# 4x2AND_OR_1.net
KiCad netlist of a schematic drawn in EAGLE
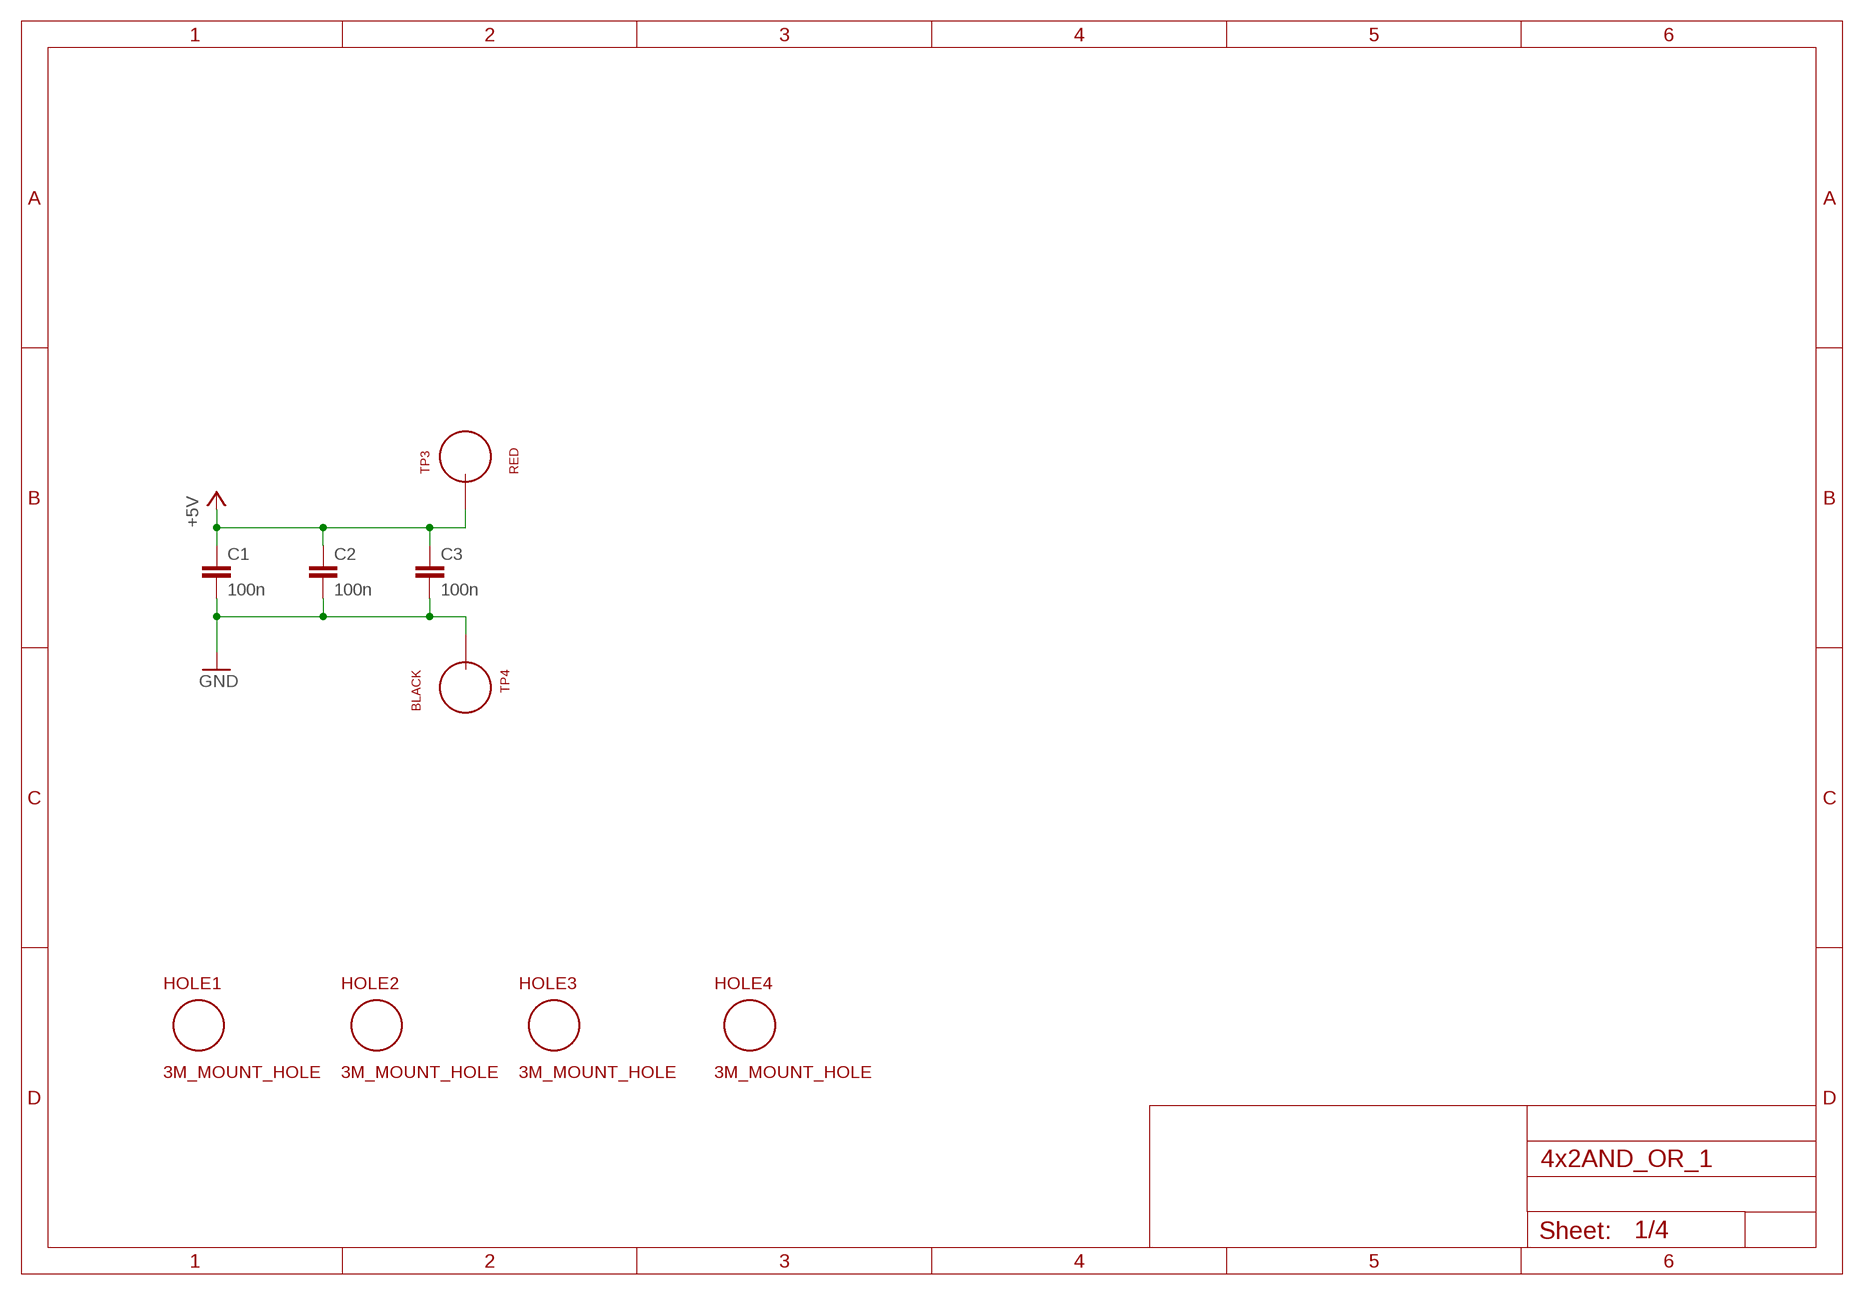
[diagram p0: schematic, sheet 1]
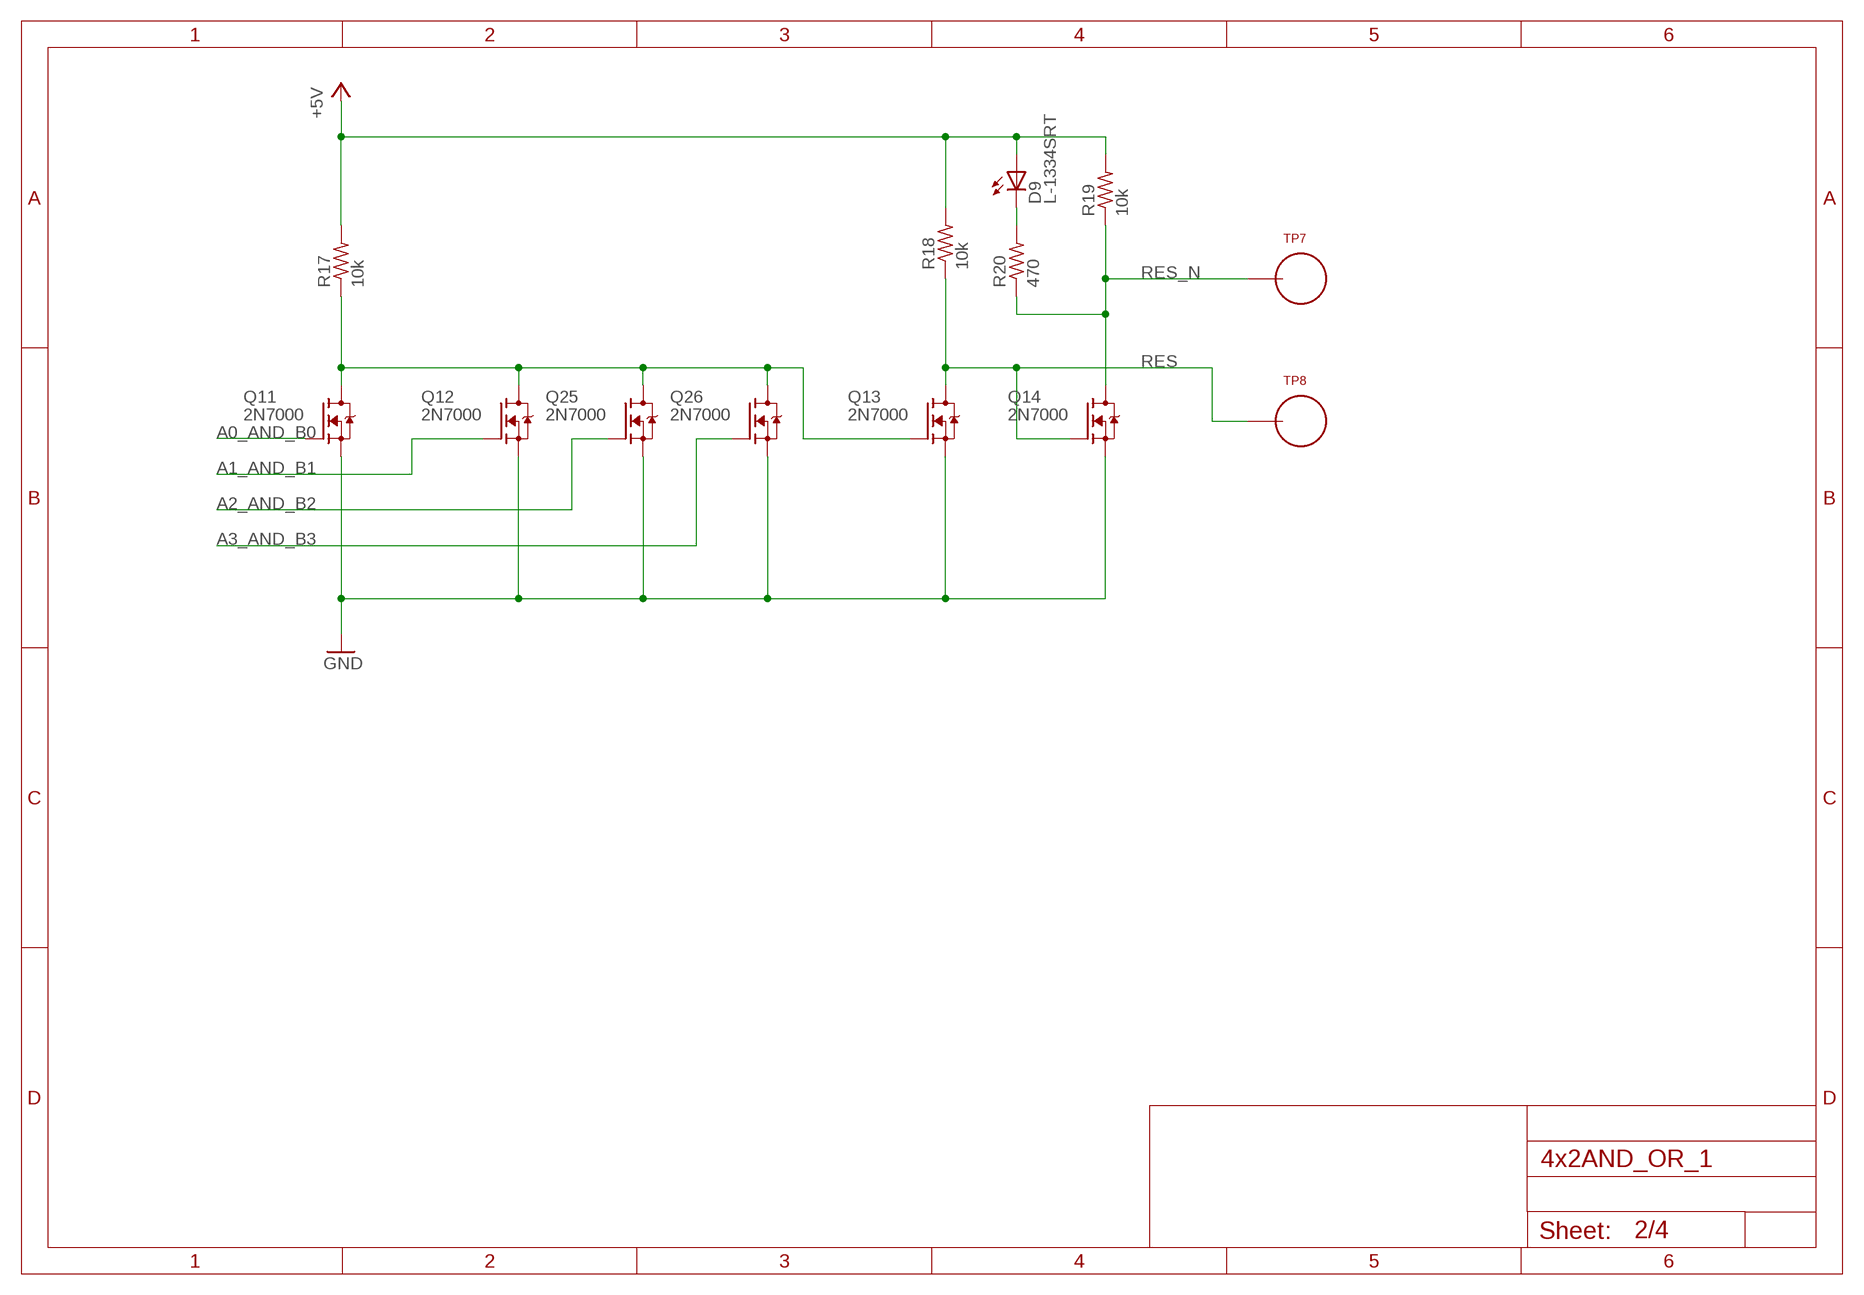
[diagram p1: schematic, sheet 2]
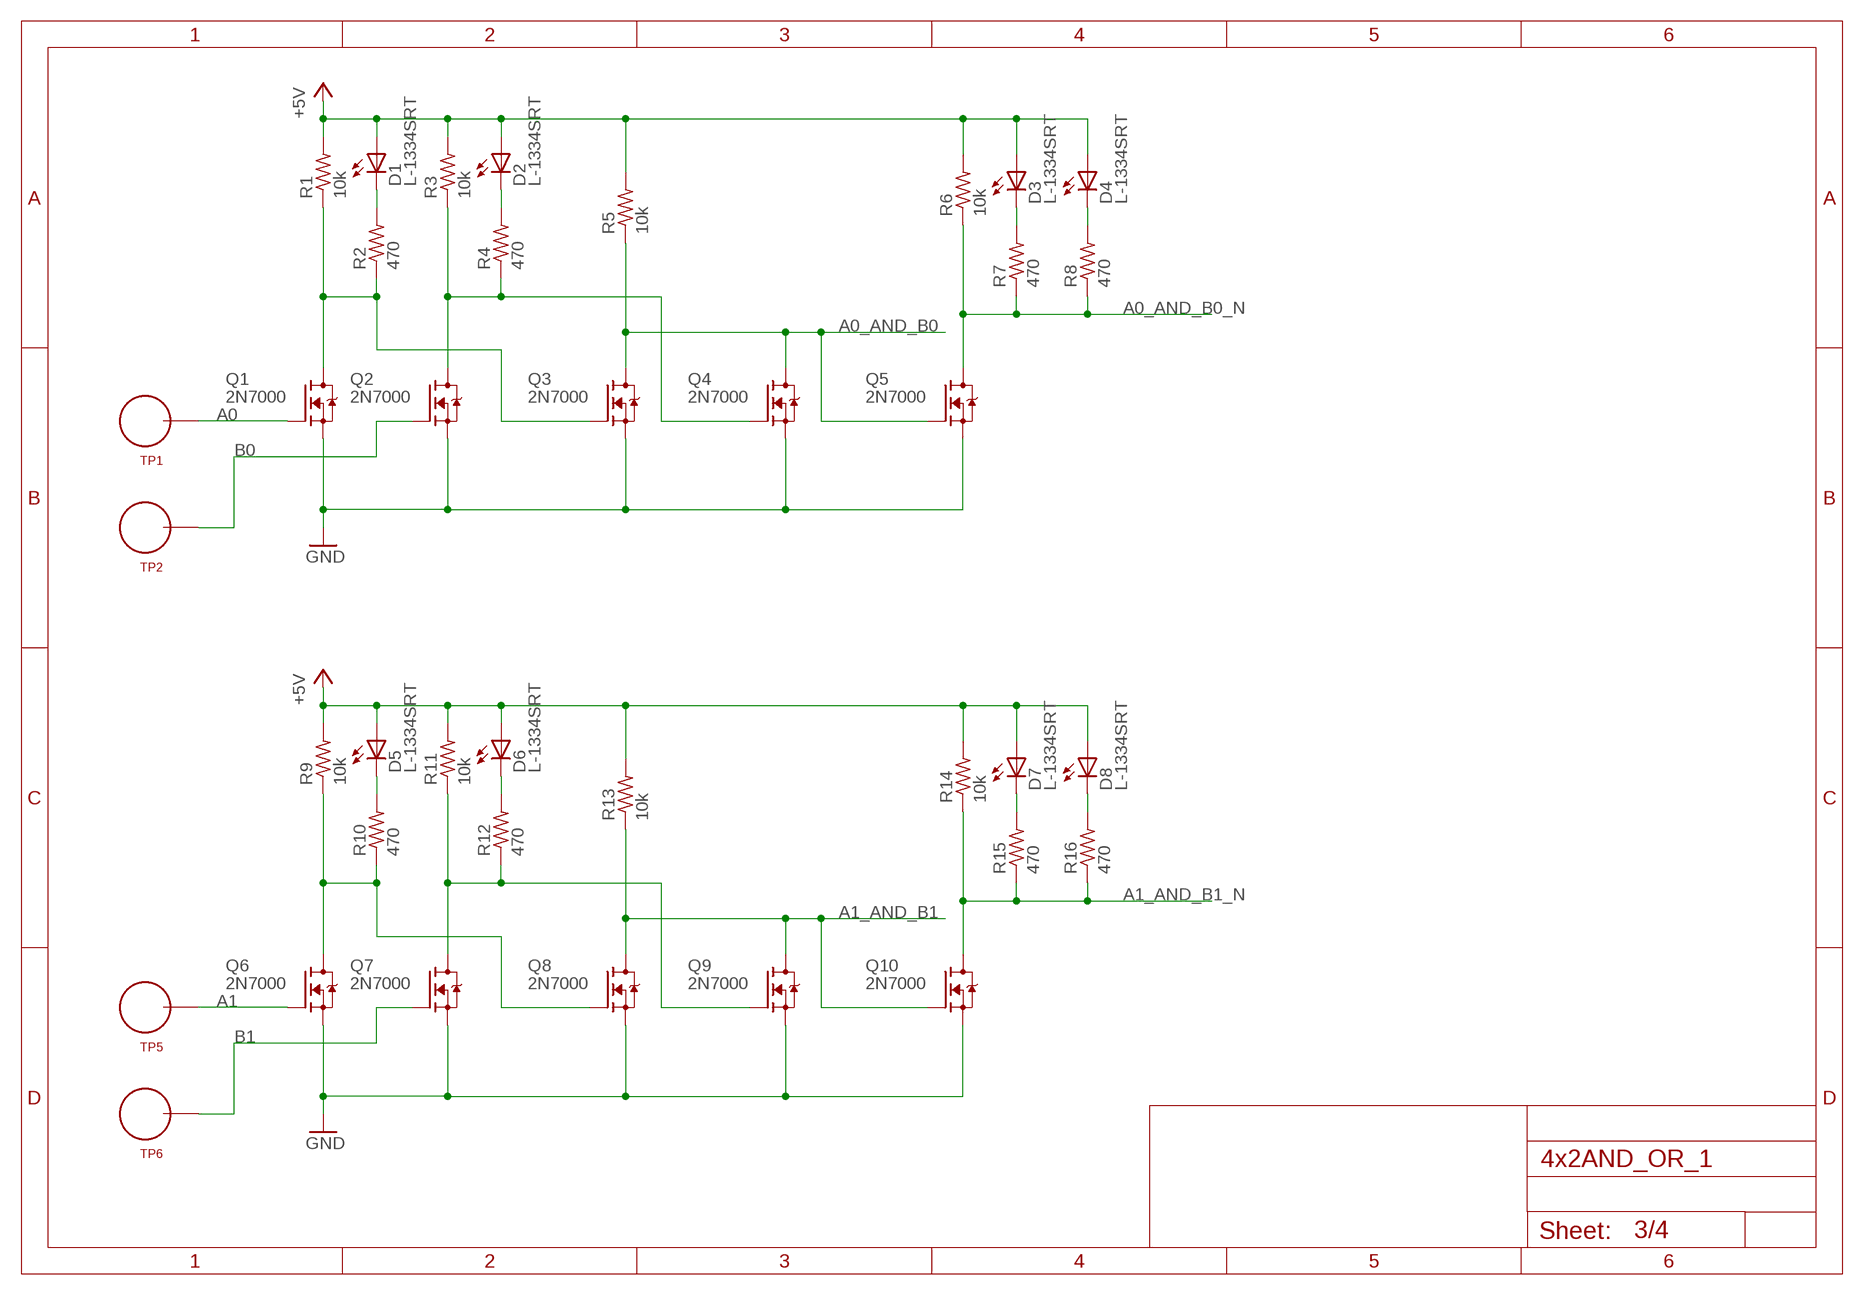
[diagram p2: schematic, sheet 3]
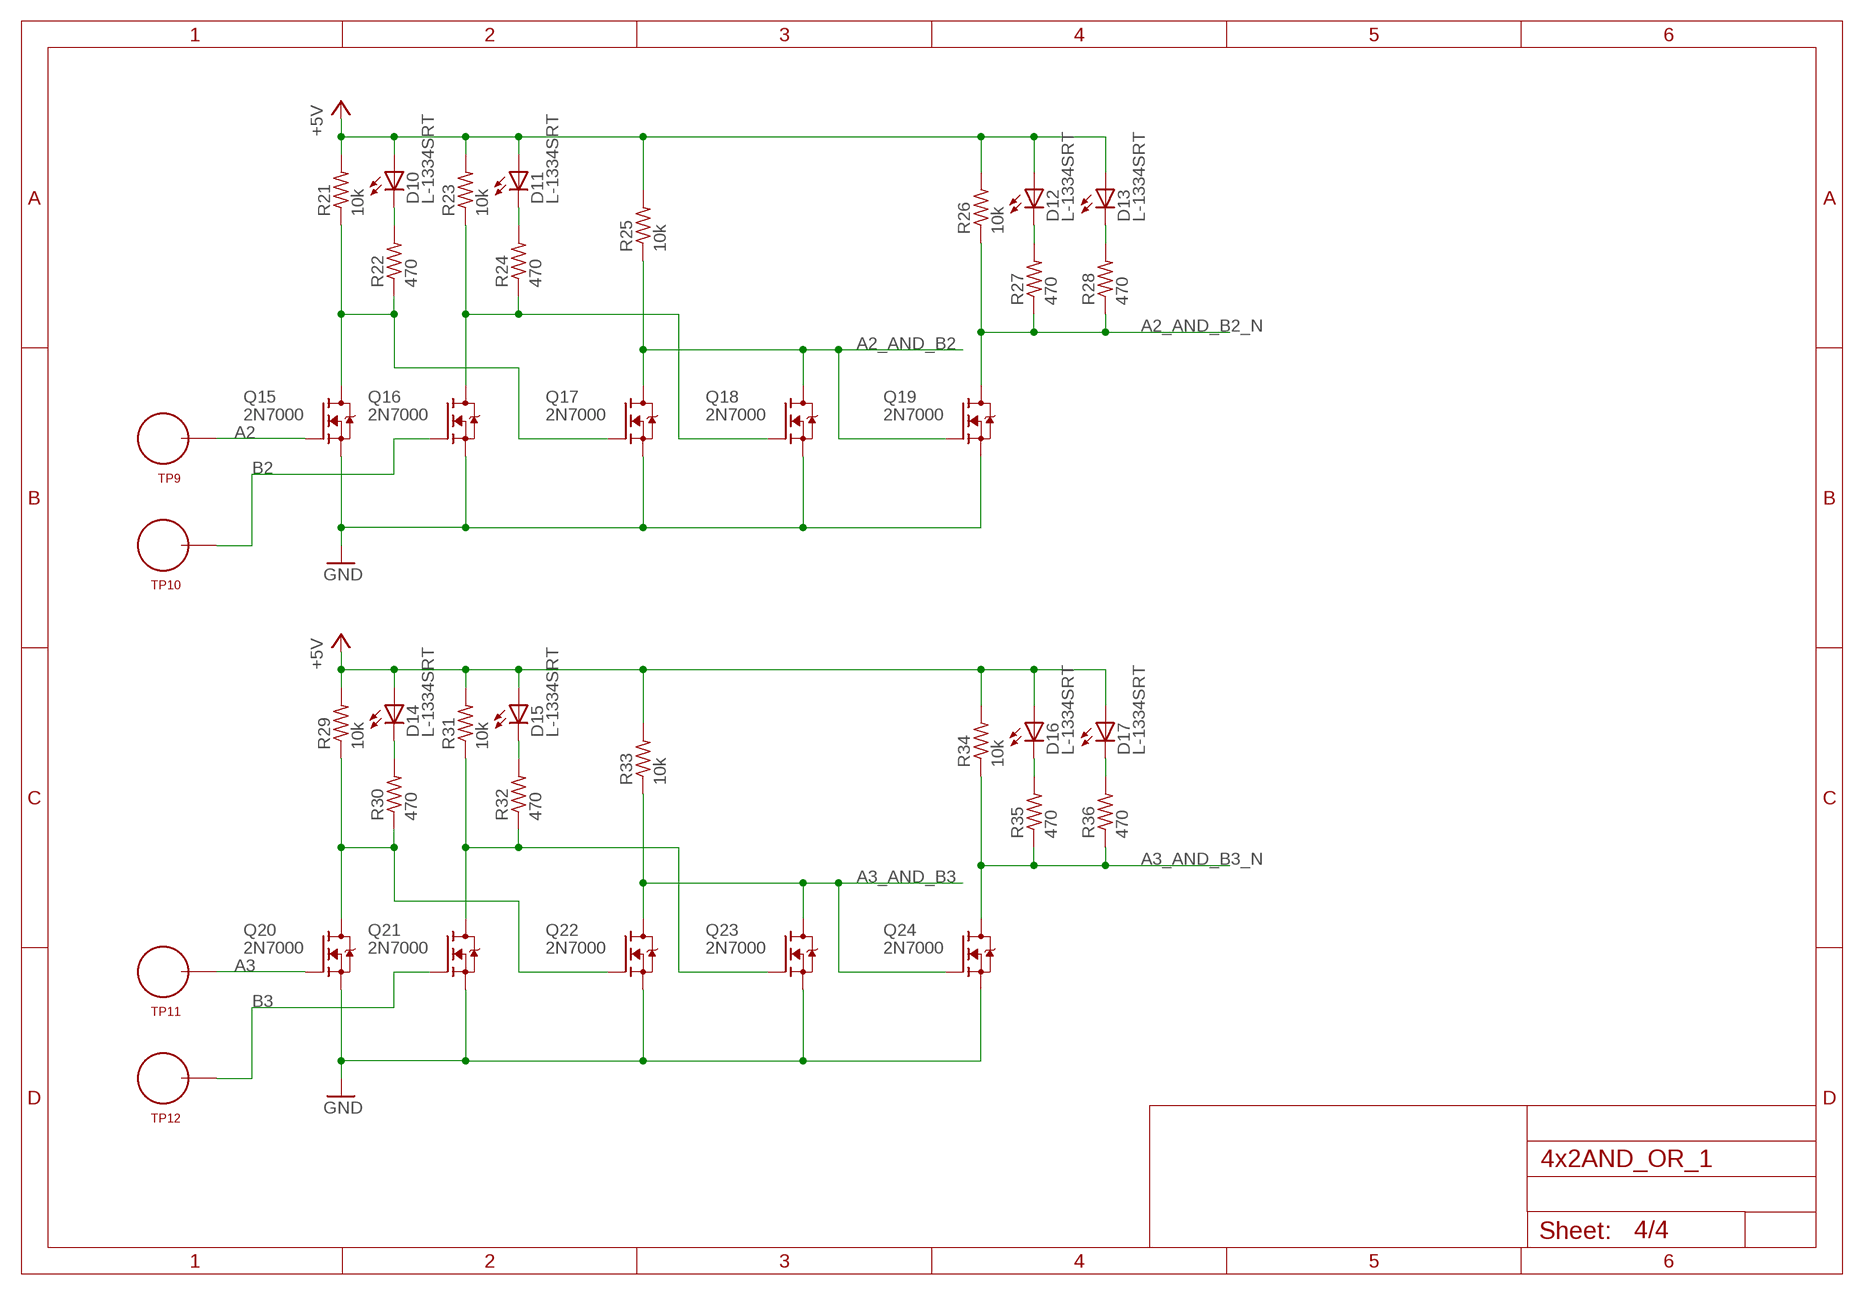
[diagram p3: schematic, sheet 4]

(export (version "E")
  (design (tool "Eeschema 10.0.6"))
  (components
    (comp (ref "D9")
      (value "L-1334SRT")
      (footprint "eagle-import:LED3MM")
      (libsource (lib "eagle-import") (part "L-1334SRT"))
    )
    (comp (ref "Q11")
      (value "2N7000")
      (footprint "eagle-import:TO92-DGS")
      (libsource (lib "eagle-import") (part "2N7000"))
    )
    (comp (ref "Q12")
      (value "2N7000")
      (footprint "eagle-import:TO92-DGS")
      (libsource (lib "eagle-import") (part "2N7000"))
    )
    (comp (ref "Q13")
      (value "2N7000")
      (footprint "eagle-import:TO92-DGS")
      (libsource (lib "eagle-import") (part "2N7000"))
    )
    (comp (ref "Q14")
      (value "2N7000")
      (footprint "eagle-import:TO92-DGS")
      (libsource (lib "eagle-import") (part "2N7000"))
    )
    (comp (ref "Q25")
      (value "2N7000")
      (footprint "eagle-import:TO92-DGS")
      (libsource (lib "eagle-import") (part "2N7000"))
    )
    (comp (ref "Q26")
      (value "2N7000")
      (footprint "eagle-import:TO92-DGS")
      (libsource (lib "eagle-import") (part "2N7000"))
    )
    (comp (ref "R17")
      (value "10k")
      (footprint "eagle-import:R_P2INCH")
      (libsource (lib "eagle-import") (part "R_P2INCH"))
    )
    (comp (ref "R18")
      (value "10k")
      (footprint "eagle-import:R_P2INCH")
      (libsource (lib "eagle-import") (part "R_P2INCH"))
    )
    (comp (ref "R19")
      (value "10k")
      (footprint "eagle-import:R_P2INCH")
      (libsource (lib "eagle-import") (part "R_P2INCH"))
    )
    (comp (ref "R20")
      (value "470")
      (footprint "eagle-import:R_P2INCH")
      (libsource (lib "eagle-import") (part "R_P2INCH"))
    )
    (comp (ref "TP7")
      (value "TEST_LOOP")
      (footprint "eagle-import:TEST_LOOP")
      (libsource (lib "eagle-import") (part "TEST_LOOP"))
    )
    (comp (ref "TP8")
      (value "TEST_LOOP")
      (footprint "eagle-import:TEST_LOOP")
      (libsource (lib "eagle-import") (part "TEST_LOOP"))
    )
    (comp (ref "C1")
      (value "100n")
      (footprint "eagle-import:CAP_P2INCH")
      (libsource (lib "eagle-import") (part "C_P2INCH"))
    )
    (comp (ref "C2")
      (value "100n")
      (footprint "eagle-import:CAP_P2INCH")
      (libsource (lib "eagle-import") (part "C_P2INCH"))
    )
    (comp (ref "C3")
      (value "100n")
      (footprint "eagle-import:CAP_P2INCH")
      (libsource (lib "eagle-import") (part "C_P2INCH"))
    )
    (comp (ref "HOLE1")
      (value "3M_MOUNT_HOLE")
      (footprint "eagle-import:3M_HOLE")
      (libsource (lib "eagle-import") (part "3M_MOUNT_HOLE"))
    )
    (comp (ref "HOLE2")
      (value "3M_MOUNT_HOLE")
      (footprint "eagle-import:3M_HOLE")
      (libsource (lib "eagle-import") (part "3M_MOUNT_HOLE"))
    )
    (comp (ref "HOLE3")
      (value "3M_MOUNT_HOLE")
      (footprint "eagle-import:3M_HOLE")
      (libsource (lib "eagle-import") (part "3M_MOUNT_HOLE"))
    )
    (comp (ref "HOLE4")
      (value "3M_MOUNT_HOLE")
      (footprint "eagle-import:3M_HOLE")
      (libsource (lib "eagle-import") (part "3M_MOUNT_HOLE"))
    )
    (comp (ref "TP3")
      (value "RED")
      (footprint "eagle-import:TEST_LOOP")
      (libsource (lib "eagle-import") (part "TEST_LOOP"))
    )
    (comp (ref "TP4")
      (value "BLACK")
      (footprint "eagle-import:TEST_LOOP")
      (libsource (lib "eagle-import") (part "TEST_LOOP"))
    )
    (comp (ref "D1")
      (value "L-1334SRT")
      (footprint "eagle-import:LED3MM")
      (libsource (lib "eagle-import") (part "L-1334SRT"))
    )
    (comp (ref "D2")
      (value "L-1334SRT")
      (footprint "eagle-import:LED3MM")
      (libsource (lib "eagle-import") (part "L-1334SRT"))
    )
    (comp (ref "D3")
      (value "L-1334SRT")
      (footprint "eagle-import:LED3MM")
      (libsource (lib "eagle-import") (part "L-1334SRT"))
    )
    (comp (ref "D4")
      (value "L-1334SRT")
      (footprint "eagle-import:LED3MM")
      (libsource (lib "eagle-import") (part "L-1334SRT"))
    )
    (comp (ref "D5")
      (value "L-1334SRT")
      (footprint "eagle-import:LED3MM")
      (libsource (lib "eagle-import") (part "L-1334SRT"))
    )
    (comp (ref "D6")
      (value "L-1334SRT")
      (footprint "eagle-import:LED3MM")
      (libsource (lib "eagle-import") (part "L-1334SRT"))
    )
    (comp (ref "D7")
      (value "L-1334SRT")
      (footprint "eagle-import:LED3MM")
      (libsource (lib "eagle-import") (part "L-1334SRT"))
    )
    (comp (ref "D8")
      (value "L-1334SRT")
      (footprint "eagle-import:LED3MM")
      (libsource (lib "eagle-import") (part "L-1334SRT"))
    )
    (comp (ref "Q1")
      (value "2N7000")
      (footprint "eagle-import:TO92-DGS")
      (libsource (lib "eagle-import") (part "2N7000"))
    )
    (comp (ref "Q2")
      (value "2N7000")
      (footprint "eagle-import:TO92-DGS")
      (libsource (lib "eagle-import") (part "2N7000"))
    )
    (comp (ref "Q3")
      (value "2N7000")
      (footprint "eagle-import:TO92-DGS")
      (libsource (lib "eagle-import") (part "2N7000"))
    )
    (comp (ref "Q4")
      (value "2N7000")
      (footprint "eagle-import:TO92-DGS")
      (libsource (lib "eagle-import") (part "2N7000"))
    )
    (comp (ref "Q5")
      (value "2N7000")
      (footprint "eagle-import:TO92-DGS")
      (libsource (lib "eagle-import") (part "2N7000"))
    )
    (comp (ref "Q6")
      (value "2N7000")
      (footprint "eagle-import:TO92-DGS")
      (libsource (lib "eagle-import") (part "2N7000"))
    )
    (comp (ref "Q7")
      (value "2N7000")
      (footprint "eagle-import:TO92-DGS")
      (libsource (lib "eagle-import") (part "2N7000"))
    )
    (comp (ref "Q8")
      (value "2N7000")
      (footprint "eagle-import:TO92-DGS")
      (libsource (lib "eagle-import") (part "2N7000"))
    )
    (comp (ref "Q9")
      (value "2N7000")
      (footprint "eagle-import:TO92-DGS")
      (libsource (lib "eagle-import") (part "2N7000"))
    )
    (comp (ref "Q10")
      (value "2N7000")
      (footprint "eagle-import:TO92-DGS")
      (libsource (lib "eagle-import") (part "2N7000"))
    )
    (comp (ref "R1")
      (value "10k")
      (footprint "eagle-import:R_P2INCH")
      (libsource (lib "eagle-import") (part "R_P2INCH"))
    )
    (comp (ref "R2")
      (value "470")
      (footprint "eagle-import:R_P2INCH")
      (libsource (lib "eagle-import") (part "R_P2INCH"))
    )
    (comp (ref "R3")
      (value "10k")
      (footprint "eagle-import:R_P2INCH")
      (libsource (lib "eagle-import") (part "R_P2INCH"))
    )
    (comp (ref "R4")
      (value "470")
      (footprint "eagle-import:R_P2INCH")
      (libsource (lib "eagle-import") (part "R_P2INCH"))
    )
    (comp (ref "R5")
      (value "10k")
      (footprint "eagle-import:R_P2INCH")
      (libsource (lib "eagle-import") (part "R_P2INCH"))
    )
    (comp (ref "R6")
      (value "10k")
      (footprint "eagle-import:R_P2INCH")
      (libsource (lib "eagle-import") (part "R_P2INCH"))
    )
    (comp (ref "R7")
      (value "470")
      (footprint "eagle-import:R_P2INCH")
      (libsource (lib "eagle-import") (part "R_P2INCH"))
    )
    (comp (ref "R8")
      (value "470")
      (footprint "eagle-import:R_P2INCH")
      (libsource (lib "eagle-import") (part "R_P2INCH"))
    )
    (comp (ref "R9")
      (value "10k")
      (footprint "eagle-import:R_P2INCH")
      (libsource (lib "eagle-import") (part "R_P2INCH"))
    )
    (comp (ref "R10")
      (value "470")
      (footprint "eagle-import:R_P2INCH")
      (libsource (lib "eagle-import") (part "R_P2INCH"))
    )
    (comp (ref "R11")
      (value "10k")
      (footprint "eagle-import:R_P2INCH")
      (libsource (lib "eagle-import") (part "R_P2INCH"))
    )
    (comp (ref "R12")
      (value "470")
      (footprint "eagle-import:R_P2INCH")
      (libsource (lib "eagle-import") (part "R_P2INCH"))
    )
    (comp (ref "R13")
      (value "10k")
      (footprint "eagle-import:R_P2INCH")
      (libsource (lib "eagle-import") (part "R_P2INCH"))
    )
    (comp (ref "R14")
      (value "10k")
      (footprint "eagle-import:R_P2INCH")
      (libsource (lib "eagle-import") (part "R_P2INCH"))
    )
    (comp (ref "R15")
      (value "470")
      (footprint "eagle-import:R_P2INCH")
      (libsource (lib "eagle-import") (part "R_P2INCH"))
    )
    (comp (ref "R16")
      (value "470")
      (footprint "eagle-import:R_P2INCH")
      (libsource (lib "eagle-import") (part "R_P2INCH"))
    )
    (comp (ref "TP1")
      (value "TEST_LOOP")
      (footprint "eagle-import:TEST_LOOP")
      (libsource (lib "eagle-import") (part "TEST_LOOP"))
    )
    (comp (ref "TP2")
      (value "TEST_LOOP")
      (footprint "eagle-import:TEST_LOOP")
      (libsource (lib "eagle-import") (part "TEST_LOOP"))
    )
    (comp (ref "TP5")
      (value "TEST_LOOP")
      (footprint "eagle-import:TEST_LOOP")
      (libsource (lib "eagle-import") (part "TEST_LOOP"))
    )
    (comp (ref "TP6")
      (value "TEST_LOOP")
      (footprint "eagle-import:TEST_LOOP")
      (libsource (lib "eagle-import") (part "TEST_LOOP"))
    )
    (comp (ref "D10")
      (value "L-1334SRT")
      (footprint "eagle-import:LED3MM")
      (libsource (lib "eagle-import") (part "L-1334SRT"))
    )
    (comp (ref "D11")
      (value "L-1334SRT")
      (footprint "eagle-import:LED3MM")
      (libsource (lib "eagle-import") (part "L-1334SRT"))
    )
    (comp (ref "D12")
      (value "L-1334SRT")
      (footprint "eagle-import:LED3MM")
      (libsource (lib "eagle-import") (part "L-1334SRT"))
    )
    (comp (ref "D13")
      (value "L-1334SRT")
      (footprint "eagle-import:LED3MM")
      (libsource (lib "eagle-import") (part "L-1334SRT"))
    )
    (comp (ref "D14")
      (value "L-1334SRT")
      (footprint "eagle-import:LED3MM")
      (libsource (lib "eagle-import") (part "L-1334SRT"))
    )
    (comp (ref "D15")
      (value "L-1334SRT")
      (footprint "eagle-import:LED3MM")
      (libsource (lib "eagle-import") (part "L-1334SRT"))
    )
    (comp (ref "D16")
      (value "L-1334SRT")
      (footprint "eagle-import:LED3MM")
      (libsource (lib "eagle-import") (part "L-1334SRT"))
    )
    (comp (ref "D17")
      (value "L-1334SRT")
      (footprint "eagle-import:LED3MM")
      (libsource (lib "eagle-import") (part "L-1334SRT"))
    )
    (comp (ref "Q15")
      (value "2N7000")
      (footprint "eagle-import:TO92-DGS")
      (libsource (lib "eagle-import") (part "2N7000"))
    )
    (comp (ref "Q16")
      (value "2N7000")
      (footprint "eagle-import:TO92-DGS")
      (libsource (lib "eagle-import") (part "2N7000"))
    )
    (comp (ref "Q17")
      (value "2N7000")
      (footprint "eagle-import:TO92-DGS")
      (libsource (lib "eagle-import") (part "2N7000"))
    )
    (comp (ref "Q18")
      (value "2N7000")
      (footprint "eagle-import:TO92-DGS")
      (libsource (lib "eagle-import") (part "2N7000"))
    )
    (comp (ref "Q19")
      (value "2N7000")
      (footprint "eagle-import:TO92-DGS")
      (libsource (lib "eagle-import") (part "2N7000"))
    )
    (comp (ref "Q20")
      (value "2N7000")
      (footprint "eagle-import:TO92-DGS")
      (libsource (lib "eagle-import") (part "2N7000"))
    )
    (comp (ref "Q21")
      (value "2N7000")
      (footprint "eagle-import:TO92-DGS")
      (libsource (lib "eagle-import") (part "2N7000"))
    )
    (comp (ref "Q22")
      (value "2N7000")
      (footprint "eagle-import:TO92-DGS")
      (libsource (lib "eagle-import") (part "2N7000"))
    )
    (comp (ref "Q23")
      (value "2N7000")
      (footprint "eagle-import:TO92-DGS")
      (libsource (lib "eagle-import") (part "2N7000"))
    )
    (comp (ref "Q24")
      (value "2N7000")
      (footprint "eagle-import:TO92-DGS")
      (libsource (lib "eagle-import") (part "2N7000"))
    )
    (comp (ref "R21")
      (value "10k")
      (footprint "eagle-import:R_P2INCH")
      (libsource (lib "eagle-import") (part "R_P2INCH"))
    )
    (comp (ref "R22")
      (value "470")
      (footprint "eagle-import:R_P2INCH")
      (libsource (lib "eagle-import") (part "R_P2INCH"))
    )
    (comp (ref "R23")
      (value "10k")
      (footprint "eagle-import:R_P2INCH")
      (libsource (lib "eagle-import") (part "R_P2INCH"))
    )
    (comp (ref "R24")
      (value "470")
      (footprint "eagle-import:R_P2INCH")
      (libsource (lib "eagle-import") (part "R_P2INCH"))
    )
    (comp (ref "R25")
      (value "10k")
      (footprint "eagle-import:R_P2INCH")
      (libsource (lib "eagle-import") (part "R_P2INCH"))
    )
    (comp (ref "R26")
      (value "10k")
      (footprint "eagle-import:R_P2INCH")
      (libsource (lib "eagle-import") (part "R_P2INCH"))
    )
    (comp (ref "R27")
      (value "470")
      (footprint "eagle-import:R_P2INCH")
      (libsource (lib "eagle-import") (part "R_P2INCH"))
    )
    (comp (ref "R28")
      (value "470")
      (footprint "eagle-import:R_P2INCH")
      (libsource (lib "eagle-import") (part "R_P2INCH"))
    )
    (comp (ref "R29")
      (value "10k")
      (footprint "eagle-import:R_P2INCH")
      (libsource (lib "eagle-import") (part "R_P2INCH"))
    )
    (comp (ref "R30")
      (value "470")
      (footprint "eagle-import:R_P2INCH")
      (libsource (lib "eagle-import") (part "R_P2INCH"))
    )
    (comp (ref "R31")
      (value "10k")
      (footprint "eagle-import:R_P2INCH")
      (libsource (lib "eagle-import") (part "R_P2INCH"))
    )
    (comp (ref "R32")
      (value "470")
      (footprint "eagle-import:R_P2INCH")
      (libsource (lib "eagle-import") (part "R_P2INCH"))
    )
    (comp (ref "R33")
      (value "10k")
      (footprint "eagle-import:R_P2INCH")
      (libsource (lib "eagle-import") (part "R_P2INCH"))
    )
    (comp (ref "R34")
      (value "10k")
      (footprint "eagle-import:R_P2INCH")
      (libsource (lib "eagle-import") (part "R_P2INCH"))
    )
    (comp (ref "R35")
      (value "470")
      (footprint "eagle-import:R_P2INCH")
      (libsource (lib "eagle-import") (part "R_P2INCH"))
    )
    (comp (ref "R36")
      (value "470")
      (footprint "eagle-import:R_P2INCH")
      (libsource (lib "eagle-import") (part "R_P2INCH"))
    )
    (comp (ref "TP9")
      (value "TEST_LOOP")
      (footprint "eagle-import:TEST_LOOP")
      (libsource (lib "eagle-import") (part "TEST_LOOP"))
    )
    (comp (ref "TP10")
      (value "TEST_LOOP")
      (footprint "eagle-import:TEST_LOOP")
      (libsource (lib "eagle-import") (part "TEST_LOOP"))
    )
    (comp (ref "TP11")
      (value "TEST_LOOP")
      (footprint "eagle-import:TEST_LOOP")
      (libsource (lib "eagle-import") (part "TEST_LOOP"))
    )
    (comp (ref "TP12")
      (value "TEST_LOOP")
      (footprint "eagle-import:TEST_LOOP")
      (libsource (lib "eagle-import") (part "TEST_LOOP"))
    )
  )
  (nets
    (net (code "1") (name "+5V") (class "Default")
      (node (ref "C1") (pin "1") (pinfunction "1_1") (pintype "passive"))
      (node (ref "C2") (pin "1") (pinfunction "1_1") (pintype "passive"))
      (node (ref "C3") (pin "1") (pinfunction "1_1") (pintype "passive"))
      (node (ref "D1") (pin "A") (pinfunction "A_A") (pintype "passive"))
      (node (ref "D10") (pin "A") (pinfunction "A_A") (pintype "passive"))
      (node (ref "D11") (pin "A") (pinfunction "A_A") (pintype "passive"))
      (node (ref "D12") (pin "A") (pinfunction "A_A") (pintype "passive"))
      (node (ref "D13") (pin "A") (pinfunction "A_A") (pintype "passive"))
      (node (ref "D14") (pin "A") (pinfunction "A_A") (pintype "passive"))
      (node (ref "D15") (pin "A") (pinfunction "A_A") (pintype "passive"))
      (node (ref "D16") (pin "A") (pinfunction "A_A") (pintype "passive"))
      (node (ref "D17") (pin "A") (pinfunction "A_A") (pintype "passive"))
      (node (ref "D2") (pin "A") (pinfunction "A_A") (pintype "passive"))
      (node (ref "D3") (pin "A") (pinfunction "A_A") (pintype "passive"))
      (node (ref "D4") (pin "A") (pinfunction "A_A") (pintype "passive"))
      (node (ref "D5") (pin "A") (pinfunction "A_A") (pintype "passive"))
      (node (ref "D6") (pin "A") (pinfunction "A_A") (pintype "passive"))
      (node (ref "D7") (pin "A") (pinfunction "A_A") (pintype "passive"))
      (node (ref "D8") (pin "A") (pinfunction "A_A") (pintype "passive"))
      (node (ref "D9") (pin "A") (pinfunction "A_A") (pintype "passive"))
      (node (ref "R1") (pin "2") (pinfunction "2_2") (pintype "passive"))
      (node (ref "R11") (pin "2") (pinfunction "2_2") (pintype "passive"))
      (node (ref "R13") (pin "2") (pinfunction "2_2") (pintype "passive"))
      (node (ref "R14") (pin "2") (pinfunction "2_2") (pintype "passive"))
      (node (ref "R17") (pin "2") (pinfunction "2_2") (pintype "passive"))
      (node (ref "R18") (pin "2") (pinfunction "2_2") (pintype "passive"))
      (node (ref "R19") (pin "2") (pinfunction "2_2") (pintype "passive"))
      (node (ref "R21") (pin "2") (pinfunction "2_2") (pintype "passive"))
      (node (ref "R23") (pin "2") (pinfunction "2_2") (pintype "passive"))
      (node (ref "R25") (pin "2") (pinfunction "2_2") (pintype "passive"))
      (node (ref "R26") (pin "2") (pinfunction "2_2") (pintype "passive"))
      (node (ref "R29") (pin "2") (pinfunction "2_2") (pintype "passive"))
      (node (ref "R3") (pin "2") (pinfunction "2_2") (pintype "passive"))
      (node (ref "R31") (pin "2") (pinfunction "2_2") (pintype "passive"))
      (node (ref "R33") (pin "2") (pinfunction "2_2") (pintype "passive"))
      (node (ref "R34") (pin "2") (pinfunction "2_2") (pintype "passive"))
      (node (ref "R5") (pin "2") (pinfunction "2_2") (pintype "passive"))
      (node (ref "R6") (pin "2") (pinfunction "2_2") (pintype "passive"))
      (node (ref "R9") (pin "2") (pinfunction "2_2") (pintype "passive"))
      (node (ref "TP3") (pin "P$1") (pinfunction "P$1_P$1") (pintype "bidirectional"))
    )
    (net (code "2") (name "A0") (class "Default")
      (node (ref "Q1") (pin "G") (pinfunction "G_G") (pintype "passive"))
      (node (ref "TP1") (pin "P$1") (pinfunction "P$1_P$1") (pintype "bidirectional"))
    )
    (net (code "3") (name "A0_AND_B0") (class "Default")
      (node (ref "Q11") (pin "G") (pinfunction "G_G") (pintype "passive"))
      (node (ref "Q3") (pin "D") (pinfunction "D_D") (pintype "passive"))
      (node (ref "Q4") (pin "D") (pinfunction "D_D") (pintype "passive"))
      (node (ref "Q5") (pin "G") (pinfunction "G_G") (pintype "passive"))
      (node (ref "R5") (pin "1") (pinfunction "1_1") (pintype "passive"))
    )
    (net (code "4") (name "A0_AND_B0_N") (class "Default")
      (node (ref "Q5") (pin "D") (pinfunction "D_D") (pintype "passive"))
      (node (ref "R6") (pin "1") (pinfunction "1_1") (pintype "passive"))
      (node (ref "R7") (pin "1") (pinfunction "1_1") (pintype "passive"))
      (node (ref "R8") (pin "1") (pinfunction "1_1") (pintype "passive"))
    )
    (net (code "5") (name "A1") (class "Default")
      (node (ref "Q6") (pin "G") (pinfunction "G_G") (pintype "passive"))
      (node (ref "TP5") (pin "P$1") (pinfunction "P$1_P$1") (pintype "bidirectional"))
    )
    (net (code "6") (name "A1_AND_B1") (class "Default")
      (node (ref "Q10") (pin "G") (pinfunction "G_G") (pintype "passive"))
      (node (ref "Q12") (pin "G") (pinfunction "G_G") (pintype "passive"))
      (node (ref "Q8") (pin "D") (pinfunction "D_D") (pintype "passive"))
      (node (ref "Q9") (pin "D") (pinfunction "D_D") (pintype "passive"))
      (node (ref "R13") (pin "1") (pinfunction "1_1") (pintype "passive"))
    )
    (net (code "7") (name "A1_AND_B1_N") (class "Default")
      (node (ref "Q10") (pin "D") (pinfunction "D_D") (pintype "passive"))
      (node (ref "R14") (pin "1") (pinfunction "1_1") (pintype "passive"))
      (node (ref "R15") (pin "1") (pinfunction "1_1") (pintype "passive"))
      (node (ref "R16") (pin "1") (pinfunction "1_1") (pintype "passive"))
    )
    (net (code "8") (name "A2") (class "Default")
      (node (ref "Q15") (pin "G") (pinfunction "G_G") (pintype "passive"))
      (node (ref "TP9") (pin "P$1") (pinfunction "P$1_P$1") (pintype "bidirectional"))
    )
    (net (code "9") (name "A2_AND_B2") (class "Default")
      (node (ref "Q17") (pin "D") (pinfunction "D_D") (pintype "passive"))
      (node (ref "Q18") (pin "D") (pinfunction "D_D") (pintype "passive"))
      (node (ref "Q19") (pin "G") (pinfunction "G_G") (pintype "passive"))
      (node (ref "Q25") (pin "G") (pinfunction "G_G") (pintype "passive"))
      (node (ref "R25") (pin "1") (pinfunction "1_1") (pintype "passive"))
    )
    (net (code "10") (name "A2_AND_B2_N") (class "Default")
      (node (ref "Q19") (pin "D") (pinfunction "D_D") (pintype "passive"))
      (node (ref "R26") (pin "1") (pinfunction "1_1") (pintype "passive"))
      (node (ref "R27") (pin "1") (pinfunction "1_1") (pintype "passive"))
      (node (ref "R28") (pin "1") (pinfunction "1_1") (pintype "passive"))
    )
    (net (code "11") (name "A3") (class "Default")
      (node (ref "Q20") (pin "G") (pinfunction "G_G") (pintype "passive"))
      (node (ref "TP11") (pin "P$1") (pinfunction "P$1_P$1") (pintype "bidirectional"))
    )
    (net (code "12") (name "A3_AND_B3") (class "Default")
      (node (ref "Q22") (pin "D") (pinfunction "D_D") (pintype "passive"))
      (node (ref "Q23") (pin "D") (pinfunction "D_D") (pintype "passive"))
      (node (ref "Q24") (pin "G") (pinfunction "G_G") (pintype "passive"))
      (node (ref "Q26") (pin "G") (pinfunction "G_G") (pintype "passive"))
      (node (ref "R33") (pin "1") (pinfunction "1_1") (pintype "passive"))
    )
    (net (code "13") (name "A3_AND_B3_N") (class "Default")
      (node (ref "Q24") (pin "D") (pinfunction "D_D") (pintype "passive"))
      (node (ref "R34") (pin "1") (pinfunction "1_1") (pintype "passive"))
      (node (ref "R35") (pin "1") (pinfunction "1_1") (pintype "passive"))
      (node (ref "R36") (pin "1") (pinfunction "1_1") (pintype "passive"))
    )
    (net (code "14") (name "B0") (class "Default")
      (node (ref "Q2") (pin "G") (pinfunction "G_G") (pintype "passive"))
      (node (ref "TP2") (pin "P$1") (pinfunction "P$1_P$1") (pintype "bidirectional"))
    )
    (net (code "15") (name "B1") (class "Default")
      (node (ref "Q7") (pin "G") (pinfunction "G_G") (pintype "passive"))
      (node (ref "TP6") (pin "P$1") (pinfunction "P$1_P$1") (pintype "bidirectional"))
    )
    (net (code "16") (name "B2") (class "Default")
      (node (ref "Q16") (pin "G") (pinfunction "G_G") (pintype "passive"))
      (node (ref "TP10") (pin "P$1") (pinfunction "P$1_P$1") (pintype "bidirectional"))
    )
    (net (code "17") (name "B3") (class "Default")
      (node (ref "Q21") (pin "G") (pinfunction "G_G") (pintype "passive"))
      (node (ref "TP12") (pin "P$1") (pinfunction "P$1_P$1") (pintype "bidirectional"))
    )
    (net (code "18") (name "GND") (class "Default")
      (node (ref "C1") (pin "2") (pinfunction "2_2") (pintype "passive"))
      (node (ref "C2") (pin "2") (pinfunction "2_2") (pintype "passive"))
      (node (ref "C3") (pin "2") (pinfunction "2_2") (pintype "passive"))
      (node (ref "Q1") (pin "S") (pinfunction "S_S") (pintype "passive"))
      (node (ref "Q10") (pin "S") (pinfunction "S_S") (pintype "passive"))
      (node (ref "Q11") (pin "S") (pinfunction "S_S") (pintype "passive"))
      (node (ref "Q12") (pin "S") (pinfunction "S_S") (pintype "passive"))
      (node (ref "Q13") (pin "S") (pinfunction "S_S") (pintype "passive"))
      (node (ref "Q14") (pin "S") (pinfunction "S_S") (pintype "passive"))
      (node (ref "Q15") (pin "S") (pinfunction "S_S") (pintype "passive"))
      (node (ref "Q16") (pin "S") (pinfunction "S_S") (pintype "passive"))
      (node (ref "Q17") (pin "S") (pinfunction "S_S") (pintype "passive"))
      (node (ref "Q18") (pin "S") (pinfunction "S_S") (pintype "passive"))
      (node (ref "Q19") (pin "S") (pinfunction "S_S") (pintype "passive"))
      (node (ref "Q2") (pin "S") (pinfunction "S_S") (pintype "passive"))
      (node (ref "Q20") (pin "S") (pinfunction "S_S") (pintype "passive"))
      (node (ref "Q21") (pin "S") (pinfunction "S_S") (pintype "passive"))
      (node (ref "Q22") (pin "S") (pinfunction "S_S") (pintype "passive"))
      (node (ref "Q23") (pin "S") (pinfunction "S_S") (pintype "passive"))
      (node (ref "Q24") (pin "S") (pinfunction "S_S") (pintype "passive"))
      (node (ref "Q25") (pin "S") (pinfunction "S_S") (pintype "passive"))
      (node (ref "Q26") (pin "S") (pinfunction "S_S") (pintype "passive"))
      (node (ref "Q3") (pin "S") (pinfunction "S_S") (pintype "passive"))
      (node (ref "Q4") (pin "S") (pinfunction "S_S") (pintype "passive"))
      (node (ref "Q5") (pin "S") (pinfunction "S_S") (pintype "passive"))
      (node (ref "Q6") (pin "S") (pinfunction "S_S") (pintype "passive"))
      (node (ref "Q7") (pin "S") (pinfunction "S_S") (pintype "passive"))
      (node (ref "Q8") (pin "S") (pinfunction "S_S") (pintype "passive"))
      (node (ref "Q9") (pin "S") (pinfunction "S_S") (pintype "passive"))
      (node (ref "TP4") (pin "P$1") (pinfunction "P$1_P$1") (pintype "bidirectional"))
    )
    (net (code "19") (name "Net-(D1-C)") (class "Default")
      (node (ref "D1") (pin "K") (pinfunction "C_K") (pintype "passive"))
      (node (ref "R2") (pin "2") (pinfunction "2_2") (pintype "passive"))
    )
    (net (code "20") (name "Net-(D2-C)") (class "Default")
      (node (ref "D2") (pin "K") (pinfunction "C_K") (pintype "passive"))
      (node (ref "R4") (pin "2") (pinfunction "2_2") (pintype "passive"))
    )
    (net (code "21") (name "Net-(D3-C)") (class "Default")
      (node (ref "D3") (pin "K") (pinfunction "C_K") (pintype "passive"))
      (node (ref "R7") (pin "2") (pinfunction "2_2") (pintype "passive"))
    )
    (net (code "22") (name "Net-(D4-C)") (class "Default")
      (node (ref "D4") (pin "K") (pinfunction "C_K") (pintype "passive"))
      (node (ref "R8") (pin "2") (pinfunction "2_2") (pintype "passive"))
    )
    (net (code "23") (name "Net-(D5-C)") (class "Default")
      (node (ref "D5") (pin "K") (pinfunction "C_K") (pintype "passive"))
      (node (ref "R10") (pin "2") (pinfunction "2_2") (pintype "passive"))
    )
    (net (code "24") (name "Net-(D6-C)") (class "Default")
      (node (ref "D6") (pin "K") (pinfunction "C_K") (pintype "passive"))
      (node (ref "R12") (pin "2") (pinfunction "2_2") (pintype "passive"))
    )
    (net (code "25") (name "Net-(D7-C)") (class "Default")
      (node (ref "D7") (pin "K") (pinfunction "C_K") (pintype "passive"))
      (node (ref "R15") (pin "2") (pinfunction "2_2") (pintype "passive"))
    )
    (net (code "26") (name "Net-(D8-C)") (class "Default")
      (node (ref "D8") (pin "K") (pinfunction "C_K") (pintype "passive"))
      (node (ref "R16") (pin "2") (pinfunction "2_2") (pintype "passive"))
    )
    (net (code "27") (name "Net-(D9-C)") (class "Default")
      (node (ref "D9") (pin "K") (pinfunction "C_K") (pintype "passive"))
      (node (ref "R20") (pin "2") (pinfunction "2_2") (pintype "passive"))
    )
    (net (code "28") (name "Net-(D10-C)") (class "Default")
      (node (ref "D10") (pin "K") (pinfunction "C_K") (pintype "passive"))
      (node (ref "R22") (pin "2") (pinfunction "2_2") (pintype "passive"))
    )
    (net (code "29") (name "Net-(D11-C)") (class "Default")
      (node (ref "D11") (pin "K") (pinfunction "C_K") (pintype "passive"))
      (node (ref "R24") (pin "2") (pinfunction "2_2") (pintype "passive"))
    )
    (net (code "30") (name "Net-(D12-C)") (class "Default")
      (node (ref "D12") (pin "K") (pinfunction "C_K") (pintype "passive"))
      (node (ref "R27") (pin "2") (pinfunction "2_2") (pintype "passive"))
    )
    (net (code "31") (name "Net-(D13-C)") (class "Default")
      (node (ref "D13") (pin "K") (pinfunction "C_K") (pintype "passive"))
      (node (ref "R28") (pin "2") (pinfunction "2_2") (pintype "passive"))
    )
    (net (code "32") (name "Net-(D14-C)") (class "Default")
      (node (ref "D14") (pin "K") (pinfunction "C_K") (pintype "passive"))
      (node (ref "R30") (pin "2") (pinfunction "2_2") (pintype "passive"))
    )
    (net (code "33") (name "Net-(D15-C)") (class "Default")
      (node (ref "D15") (pin "K") (pinfunction "C_K") (pintype "passive"))
      (node (ref "R32") (pin "2") (pinfunction "2_2") (pintype "passive"))
    )
    (net (code "34") (name "Net-(D16-C)") (class "Default")
      (node (ref "D16") (pin "K") (pinfunction "C_K") (pintype "passive"))
      (node (ref "R35") (pin "2") (pinfunction "2_2") (pintype "passive"))
    )
    (net (code "35") (name "Net-(D17-C)") (class "Default")
      (node (ref "D17") (pin "K") (pinfunction "C_K") (pintype "passive"))
      (node (ref "R36") (pin "2") (pinfunction "2_2") (pintype "passive"))
    )
    (net (code "36") (name "Net-(Q1-PadD)") (class "Default")
      (node (ref "Q1") (pin "D") (pinfunction "D_D") (pintype "passive"))
      (node (ref "Q3") (pin "G") (pinfunction "G_G") (pintype "passive"))
      (node (ref "R1") (pin "1") (pinfunction "1_1") (pintype "passive"))
      (node (ref "R2") (pin "1") (pinfunction "1_1") (pintype "passive"))
    )
    (net (code "37") (name "Net-(Q2-PadD)") (class "Default")
      (node (ref "Q2") (pin "D") (pinfunction "D_D") (pintype "passive"))
      (node (ref "Q4") (pin "G") (pinfunction "G_G") (pintype "passive"))
      (node (ref "R3") (pin "1") (pinfunction "1_1") (pintype "passive"))
      (node (ref "R4") (pin "1") (pinfunction "1_1") (pintype "passive"))
    )
    (net (code "38") (name "Net-(Q6-PadD)") (class "Default")
      (node (ref "Q6") (pin "D") (pinfunction "D_D") (pintype "passive"))
      (node (ref "Q8") (pin "G") (pinfunction "G_G") (pintype "passive"))
      (node (ref "R10") (pin "1") (pinfunction "1_1") (pintype "passive"))
      (node (ref "R9") (pin "1") (pinfunction "1_1") (pintype "passive"))
    )
    (net (code "39") (name "Net-(Q7-PadD)") (class "Default")
      (node (ref "Q7") (pin "D") (pinfunction "D_D") (pintype "passive"))
      (node (ref "Q9") (pin "G") (pinfunction "G_G") (pintype "passive"))
      (node (ref "R11") (pin "1") (pinfunction "1_1") (pintype "passive"))
      (node (ref "R12") (pin "1") (pinfunction "1_1") (pintype "passive"))
    )
    (net (code "40") (name "Net-(Q11-PadD)") (class "Default")
      (node (ref "Q11") (pin "D") (pinfunction "D_D") (pintype "passive"))
      (node (ref "Q12") (pin "D") (pinfunction "D_D") (pintype "passive"))
      (node (ref "Q13") (pin "G") (pinfunction "G_G") (pintype "passive"))
      (node (ref "Q25") (pin "D") (pinfunction "D_D") (pintype "passive"))
      (node (ref "Q26") (pin "D") (pinfunction "D_D") (pintype "passive"))
      (node (ref "R17") (pin "1") (pinfunction "1_1") (pintype "passive"))
    )
    (net (code "41") (name "Net-(Q15-PadD)") (class "Default")
      (node (ref "Q15") (pin "D") (pinfunction "D_D") (pintype "passive"))
      (node (ref "Q17") (pin "G") (pinfunction "G_G") (pintype "passive"))
      (node (ref "R21") (pin "1") (pinfunction "1_1") (pintype "passive"))
      (node (ref "R22") (pin "1") (pinfunction "1_1") (pintype "passive"))
    )
    (net (code "42") (name "Net-(Q16-PadD)") (class "Default")
      (node (ref "Q16") (pin "D") (pinfunction "D_D") (pintype "passive"))
      (node (ref "Q18") (pin "G") (pinfunction "G_G") (pintype "passive"))
      (node (ref "R23") (pin "1") (pinfunction "1_1") (pintype "passive"))
      (node (ref "R24") (pin "1") (pinfunction "1_1") (pintype "passive"))
    )
    (net (code "43") (name "Net-(Q20-PadD)") (class "Default")
      (node (ref "Q20") (pin "D") (pinfunction "D_D") (pintype "passive"))
      (node (ref "Q22") (pin "G") (pinfunction "G_G") (pintype "passive"))
      (node (ref "R29") (pin "1") (pinfunction "1_1") (pintype "passive"))
      (node (ref "R30") (pin "1") (pinfunction "1_1") (pintype "passive"))
    )
    (net (code "44") (name "Net-(Q21-PadD)") (class "Default")
      (node (ref "Q21") (pin "D") (pinfunction "D_D") (pintype "passive"))
      (node (ref "Q23") (pin "G") (pinfunction "G_G") (pintype "passive"))
      (node (ref "R31") (pin "1") (pinfunction "1_1") (pintype "passive"))
      (node (ref "R32") (pin "1") (pinfunction "1_1") (pintype "passive"))
    )
    (net (code "45") (name "RES") (class "Default")
      (node (ref "Q13") (pin "D") (pinfunction "D_D") (pintype "passive"))
      (node (ref "Q14") (pin "G") (pinfunction "G_G") (pintype "passive"))
      (node (ref "R18") (pin "1") (pinfunction "1_1") (pintype "passive"))
      (node (ref "TP8") (pin "P$1") (pinfunction "P$1_P$1") (pintype "bidirectional"))
    )
    (net (code "46") (name "RES_N") (class "Default")
      (node (ref "Q14") (pin "D") (pinfunction "D_D") (pintype "passive"))
      (node (ref "R19") (pin "1") (pinfunction "1_1") (pintype "passive"))
      (node (ref "R20") (pin "1") (pinfunction "1_1") (pintype "passive"))
      (node (ref "TP7") (pin "P$1") (pinfunction "P$1_P$1") (pintype "bidirectional"))
    )
  )
)
